# ACDC.net
KiCad netlist of a schematic drawn in EasyEDA Pro
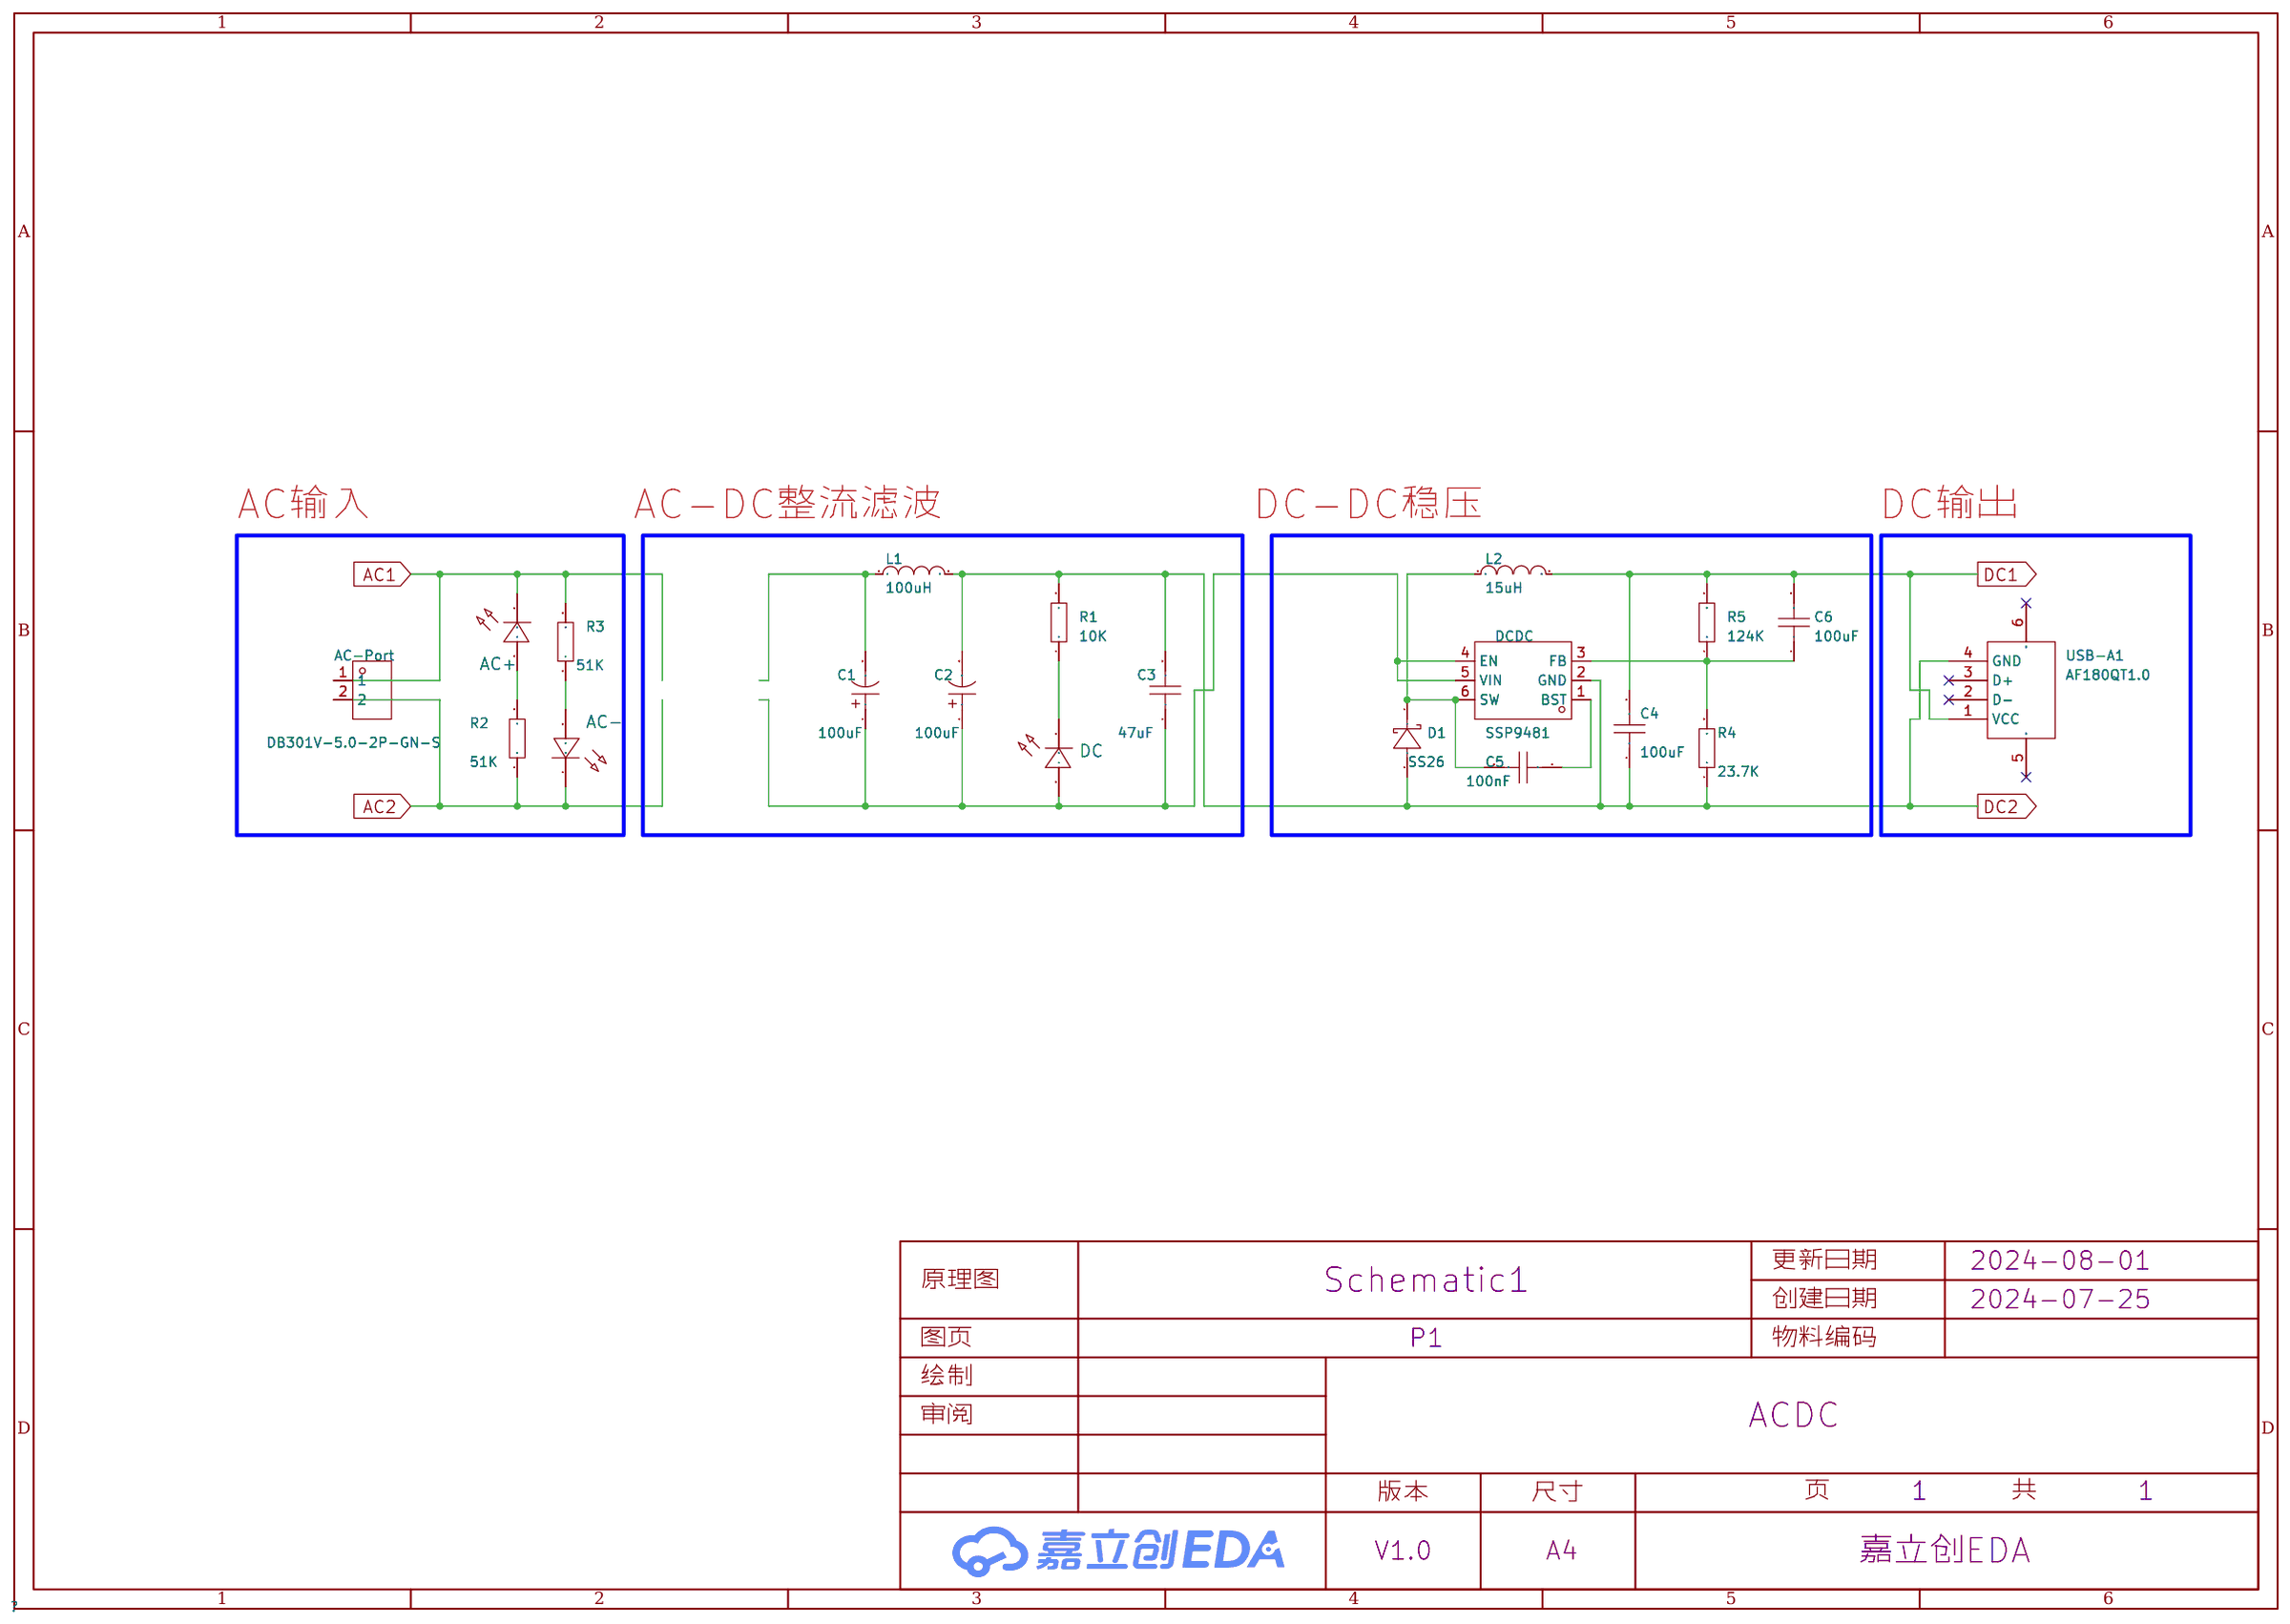
[diagram p0: schematic sheet]

(export (version "E")
  (design (tool "Eeschema 10.0.6"))
  (components
    (comp (ref "AC+")
      (value "~")
      (footprint "easyedapro:LED_0603")
      (libsource (lib "easyedapro") (part "LED_R"))
    )
    (comp (ref "AC-")
      (value "~")
      (footprint "easyedapro:LED_0603")
      (libsource (lib "easyedapro") (part "LED_R"))
    )
    (comp (ref "AC-Port")
      (value "DB301V-5.0-2P-GN-S")
      (footprint "easyedapro:CONN-TH_2P-P5.00_DB301V-5.0-2P-GN-S")
      (fields (field (name "Manufacturer") "DORABO(地博电气)"))
      (libsource (lib "easyedapro") (part "DB301V-5.0-2P-GN-S"))
    )
    (comp (ref "C1")
      (value "100uF")
      (footprint "easyedapro:CAP-TH_BD6.3-P2.50-D0.6-FD-1")
      (description "容值:33uF;精度:±20%;额定电压:63V;")
      (fields
        (field (name "Manufacturer Part") "SPT1JM330E08ORVZC")
        (field (name "Manufacturer") "Yunxing(云星)")
      )
      (libsource (lib "easyedapro") (part "SPT1JM330E08ORVZC"))
    )
    (comp (ref "C2")
      (value "100uF")
      (footprint "easyedapro:CAP-TH_BD6.3-P2.50-D0.6-FD-1")
      (description "容值:33uF;精度:±20%;额定电压:63V;")
      (fields
        (field (name "Manufacturer Part") "SPT1JM330E08ORVZC")
        (field (name "Manufacturer") "Yunxing(云星)")
      )
      (libsource (lib "easyedapro") (part "SPT1JM330E08ORVZC"))
    )
    (comp (ref "C3")
      (value "47uF")
      (footprint "easyedapro:C0603")
      (libsource (lib "easyedapro") (part "CapAcitance"))
    )
    (comp (ref "C4")
      (value "100uF")
      (footprint "easyedapro:C0603")
      (libsource (lib "easyedapro") (part "CapAcitance"))
    )
    (comp (ref "C5")
      (value "100nF")
      (footprint "easyedapro:C0603")
      (libsource (lib "easyedapro") (part "CapAcitance"))
    )
    (comp (ref "C6")
      (value "100uF")
      (footprint "easyedapro:C0603")
      (libsource (lib "easyedapro") (part "CapAcitance"))
    )
    (comp (ref "D1")
      (value "SS26")
      (footprint "easyedapro:SMA_L4.2-W2.6-LS5.3-RD")
      (description "二极管配置:独立式;正向压降(Vf):700mV@2A;直流反向耐压(Vr):60V;平均整流电流(Io):2A;")
      (fields (field (name "Manufacturer") "CJ(江苏长电/长晶)"))
      (libsource (lib "easyedapro") (part "SS26_C2923952"))
    )
    (comp (ref "DC")
      (value "~")
      (footprint "easyedapro:LED_0603")
      (libsource (lib "easyedapro") (part "LED_R"))
    )
    (comp (ref "DCDC")
      (value "SSP9481")
      (footprint "easyedapro:SOT-23-6_L2.9-W1.6-P0.95-LS2.8-BR")
      (description "输入电压:4.5V~80V;输出电流(最大值):1A;")
      (fields (field (name "Manufacturer") "Siproin(上海矽朋)"))
      (libsource (lib "easyedapro") (part "SSP9481"))
    )
    (comp (ref "L1")
      (value "100uH")
      (footprint "easyedapro:IND-SMD_L11.6-W10.1")
      (description "电感值:33uH;精度:±20%;额定电流:3.2A;饱和电流(Isat):5A;直流电阻(DCR):110mΩ;")
      (fields (field (name "Manufacturer Part") "BCIHP1040SC-330M") (field (name "Manufacturer") "BC(台湾诚阳)"))
      (libsource (lib "easyedapro") (part "BCIHP1040SC-330M"))
    )
    (comp (ref "L2")
      (value "15uH")
      (footprint "easyedapro:L0603")
      (libsource (lib "easyedapro") (part "SDFL1608S100KTF"))
    )
    (comp (ref "R1") (value "10K") (footprint "easyedapro:R0603") (libsource (lib "easyedapro") (part "电阻")))
    (comp (ref "R2") (value "51K") (footprint "easyedapro:R0603") (libsource (lib "easyedapro") (part "电阻")))
    (comp (ref "R3") (value "51K") (footprint "easyedapro:R0603") (libsource (lib "easyedapro") (part "电阻")))
    (comp (ref "R4")
      (value "23.7K")
      (footprint "easyedapro:R0603")
      (libsource (lib "easyedapro") (part "电阻"))
    )
    (comp (ref "R5") (value "124K") (footprint "easyedapro:R0603") (libsource (lib "easyedapro") (part "电阻")))
    (comp (ref "USB-A1")
      (value "AF180QT1.0")
      (footprint "easyedapro:USB-A-SMD_AF180QT1.0")
      (description "连接器类型:Type-A;标准:USB 2.0;公母:母;端口数量:1;触点数量:4P;安装方式:卧贴;额定电流 - 电源:-;工作温度范围:-;")
      (fields (field (name "Manufacturer") "SHOU HAN(首韩)"))
      (libsource (lib "easyedapro") (part "AF180QT1.0"))
    )
  )
  (nets
    (net (code "1") (name "AC1") (class "Default")
      (node (ref "AC+") (pin "1") (pinfunction "C_1") (pintype "input"))
      (node (ref "AC-Port") (pin "1") (pinfunction "1_1") (pintype "unspecified"))
      (node (ref "R3") (pin "2") (pinfunction "2_2") (pintype "input"))
    )
    (net (code "2") (name "AC2") (class "Default")
      (node (ref "AC-") (pin "1") (pinfunction "C_1") (pintype "input"))
      (node (ref "AC-Port") (pin "2") (pinfunction "2_2") (pintype "unspecified"))
      (node (ref "R2") (pin "1") (pinfunction "1_1") (pintype "input"))
    )
    (net (code "3") (name "DC1") (class "Default")
      (node (ref "C4") (pin "2") (pinfunction "2_2") (pintype "input"))
      (node (ref "C6") (pin "2") (pinfunction "2_2") (pintype "input"))
      (node (ref "L2") (pin "2") (pinfunction "2_2") (pintype "unspecified"))
      (node (ref "R5") (pin "2") (pinfunction "2_2") (pintype "input"))
      (node (ref "USB-A1") (pin "1") (pinfunction "VCC_1") (pintype "input"))
    )
    (net (code "4") (name "DC2") (class "Default")
      (node (ref "C2") (pin "2") (pinfunction "2_2") (pintype "input"))
      (node (ref "C3") (pin "2") (pinfunction "2_2") (pintype "input"))
      (node (ref "C4") (pin "1") (pinfunction "1_1") (pintype "input"))
      (node (ref "D1") (pin "2") (pinfunction "A_2") (pintype "unspecified"))
      (node (ref "DCDC") (pin "2") (pinfunction "GND_2") (pintype "unspecified"))
      (node (ref "L1") (pin "2") (pinfunction "2_2") (pintype "unspecified"))
      (node (ref "R1") (pin "2") (pinfunction "2_2") (pintype "input"))
      (node (ref "R4") (pin "1") (pinfunction "1_1") (pintype "input"))
      (node (ref "USB-A1") (pin "4") (pinfunction "GND_4") (pintype "input"))
    )
    (net (code "5") (name "Net-(AC+-A)") (class "Default")
      (node (ref "AC+") (pin "2") (pinfunction "A_2") (pintype "input"))
      (node (ref "R2") (pin "2") (pinfunction "2_2") (pintype "input"))
    )
    (net (code "6") (name "Net-(AC--A)") (class "Default")
      (node (ref "AC-") (pin "2") (pinfunction "A_2") (pintype "input"))
      (node (ref "R3") (pin "1") (pinfunction "1_1") (pintype "input"))
    )
    (net (code "7") (name "Net-(C1-Pad2)") (class "Default")
      (node (ref "C1") (pin "2") (pinfunction "2_2") (pintype "input"))
      (node (ref "L1") (pin "1") (pinfunction "1_1") (pintype "unspecified"))
    )
    (net (code "8") (name "Net-(D1-K)") (class "Default")
      (node (ref "C5") (pin "2") (pinfunction "2_2") (pintype "input"))
      (node (ref "D1") (pin "1") (pinfunction "K_1") (pintype "unspecified"))
      (node (ref "DCDC") (pin "6") (pinfunction "SW_6") (pintype "unspecified"))
      (node (ref "L2") (pin "1") (pinfunction "1_1") (pintype "unspecified"))
    )
    (net (code "9") (name "Net-(DC-A)") (class "Default")
      (node (ref "C1") (pin "1") (pinfunction "1_1") (pintype "input"))
      (node (ref "C2") (pin "1") (pinfunction "1_1") (pintype "input"))
      (node (ref "C3") (pin "1") (pinfunction "1_1") (pintype "input"))
      (node (ref "DC") (pin "2") (pinfunction "A_2") (pintype "input"))
      (node (ref "DCDC") (pin "4") (pinfunction "EN_4") (pintype "unspecified"))
      (node (ref "DCDC") (pin "5") (pinfunction "VIN_5") (pintype "unspecified"))
    )
    (net (code "10") (name "Net-(DC-C)") (class "Default")
      (node (ref "DC") (pin "1") (pinfunction "C_1") (pintype "input"))
      (node (ref "R1") (pin "1") (pinfunction "1_1") (pintype "input"))
    )
    (net (code "11") (name "Net-(DCDC-BST)") (class "Default")
      (node (ref "C5") (pin "1") (pinfunction "1_1") (pintype "input"))
      (node (ref "DCDC") (pin "1") (pinfunction "BST_1") (pintype "unspecified"))
    )
    (net (code "12") (name "Net-(DCDC-FB)") (class "Default")
      (node (ref "C6") (pin "1") (pinfunction "1_1") (pintype "input"))
      (node (ref "DCDC") (pin "3") (pinfunction "FB_3") (pintype "unspecified"))
      (node (ref "R4") (pin "2") (pinfunction "2_2") (pintype "input"))
      (node (ref "R5") (pin "1") (pinfunction "1_1") (pintype "input"))
    )
    (net (code "13") (name "unconnected-(USB-A1-D+-Pad3)") (class "Default")
      (node (ref "USB-A1") (pin "3") (pinfunction "D+_3") (pintype "input+no_connect"))
    )
    (net (code "14") (name "unconnected-(USB-A1-D--Pad2)") (class "Default")
      (node (ref "USB-A1") (pin "2") (pinfunction "D-_2") (pintype "input+no_connect"))
    )
    (net (code "15") (name "unconnected-(USB-A1-SH1-Pad5)") (class "Default")
      (node (ref "USB-A1") (pin "5") (pinfunction "SH1_5") (pintype "unspecified+no_connect"))
    )
    (net (code "16") (name "unconnected-(USB-A1-SH2-Pad6)") (class "Default")
      (node (ref "USB-A1") (pin "6") (pinfunction "SH2_6") (pintype "unspecified+no_connect"))
    )
  )
)
